# USB_ULPI_Interface.net
KiCad netlist of a schematic drawn in Altium Designer
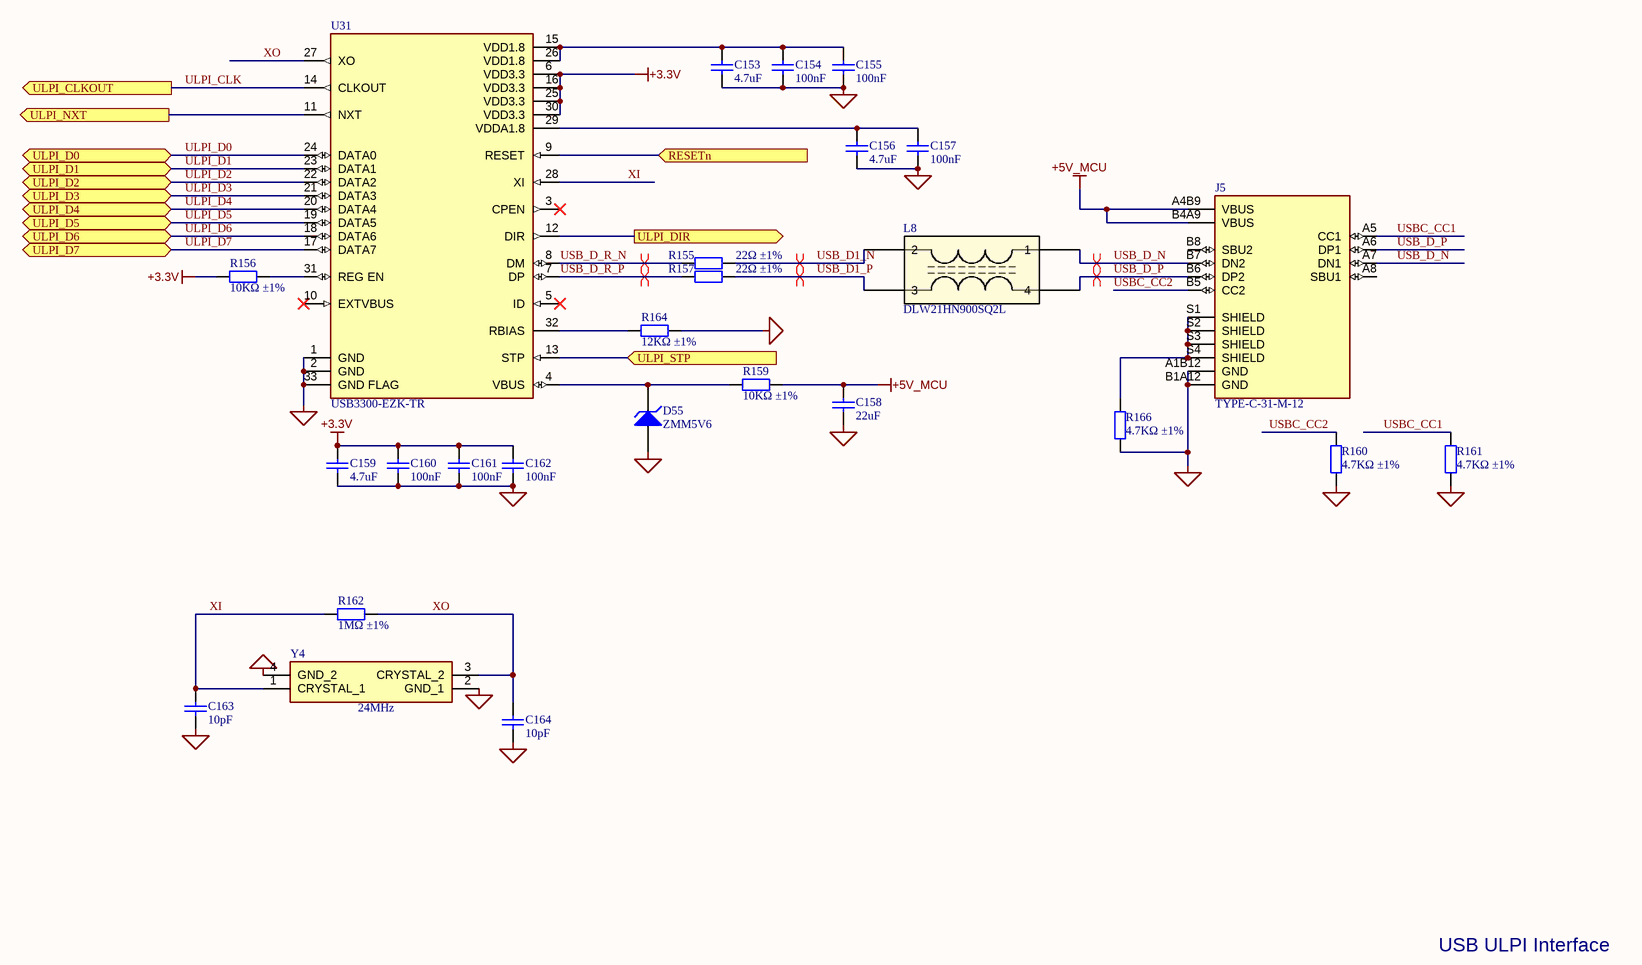
[diagram p0: USB_ULPI_Interface.SchDoc]

(export (version "E")
  (design (tool "Eeschema 10.0.6"))
  (components
    (comp (ref "C153")
      (value "4.7uF")
      (footprint "0603_C")
      (description "Chip capacitors")
      (fields
        (field (name "MANUFACTURER") "Samsung Electro-Mechanics")
        (field (name "PARTNUMBER") "CL10A475KO8NNNC")
      )
      (libsource (lib "Cap") (part "0603 4.7uF (475) 10% 16V"))
    )
    (comp (ref "C154")
      (value "100nF")
      (footprint "0402_C")
      (description "Chip capacitors")
      (fields
        (field (name "MANUFACTURER") "Samsung Electro-Mechanics")
        (field (name "PARTNUMBER") "CL05B104KO5NNNC")
      )
      (libsource (lib "Cap") (part "0402 100nF (104) 10% 16V"))
    )
    (comp (ref "C155")
      (value "100nF")
      (footprint "0402_C")
      (description "Chip capacitors")
      (fields
        (field (name "MANUFACTURER") "Samsung Electro-Mechanics")
        (field (name "PARTNUMBER") "CL05B104KO5NNNC")
      )
      (libsource (lib "Cap") (part "0402 100nF (104) 10% 16V"))
    )
    (comp (ref "C156")
      (value "4.7uF")
      (footprint "0603_C")
      (description "Chip capacitors")
      (fields
        (field (name "MANUFACTURER") "Samsung Electro-Mechanics")
        (field (name "PARTNUMBER") "CL10A475KO8NNNC")
      )
      (libsource (lib "Cap") (part "0603 4.7uF (475) 10% 16V"))
    )
    (comp (ref "C157")
      (value "100nF")
      (footprint "0402_C")
      (description "Chip capacitors")
      (fields
        (field (name "MANUFACTURER") "Samsung Electro-Mechanics")
        (field (name "PARTNUMBER") "CL05B104KO5NNNC")
      )
      (libsource (lib "Cap") (part "0402 100nF (104) 10% 16V"))
    )
    (comp (ref "C158")
      (value "22uF")
      (footprint "0805_C")
      (description "Chip capacitors")
      (fields
        (field (name "MANUFACTURER") "Samsung Electro-Mechanics")
        (field (name "PARTNUMBER") "CL21A226MAQNNNE")
      )
      (libsource (lib "Cap") (part "0805 22uF (226) 20% 25V"))
    )
    (comp (ref "C159")
      (value "4.7uF")
      (footprint "0603_C")
      (description "Chip capacitors")
      (fields
        (field (name "MANUFACTURER") "Samsung Electro-Mechanics")
        (field (name "PARTNUMBER") "CL10A475KO8NNNC")
      )
      (libsource (lib "Cap") (part "0603 4.7uF (475) 10% 16V"))
    )
    (comp (ref "C160")
      (value "100nF")
      (footprint "0402_C")
      (description "Chip capacitors")
      (fields
        (field (name "MANUFACTURER") "Samsung Electro-Mechanics")
        (field (name "PARTNUMBER") "CL05B104KO5NNNC")
      )
      (libsource (lib "Cap") (part "0402 100nF (104) 10% 16V"))
    )
    (comp (ref "C161")
      (value "100nF")
      (footprint "0402_C")
      (description "Chip capacitors")
      (fields
        (field (name "MANUFACTURER") "Samsung Electro-Mechanics")
        (field (name "PARTNUMBER") "CL05B104KO5NNNC")
      )
      (libsource (lib "Cap") (part "0402 100nF (104) 10% 16V"))
    )
    (comp (ref "C162")
      (value "100nF")
      (footprint "0402_C")
      (description "Chip capacitors")
      (fields
        (field (name "MANUFACTURER") "Samsung Electro-Mechanics")
        (field (name "PARTNUMBER") "CL05B104KO5NNNC")
      )
      (libsource (lib "Cap") (part "0402 100nF (104) 10% 16V"))
    )
    (comp (ref "C163")
      (value "10pF")
      (footprint "0402_C")
      (description "Chip capacitors")
      (fields
        (field (name "MANUFACTURER") "Samsung Electro-Mechanics")
        (field (name "MANUFACTURER PART NUMBER") "CL05C100JB5NNNC")
      )
      (libsource (lib "Cap") (part "0402 10pF (100) 5% 50V"))
    )
    (comp (ref "C164")
      (value "10pF")
      (footprint "0402_C")
      (description "Chip capacitors")
      (fields
        (field (name "MANUFACTURER") "Samsung Electro-Mechanics")
        (field (name "MANUFACTURER PART NUMBER") "CL05C100JB5NNNC")
      )
      (libsource (lib "Cap") (part "0402 10pF (100) 5% 50V"))
    )
    (comp (ref "D55")
      (value "ZMM5V6")
      (footprint "LL-34")
      (description "500mW - 0.1uA @ 1V 5.6V LL-34 Zener Diodes ROHS")
      (libsource (lib "Zener") (part "LL-34 ZMM5V6"))
    )
    (comp (ref "J5")
      (value "TYPE-C-31-M-12")
      (footprint "HRO_TYPE-C-31-M-12")
      (description "USB Connectors 24 Receptacle 1 8.94*7.3mm RoHS")
      (fields (field (name "MF") "HRO Electronics Co., Ltd."))
      (libsource (lib "Universal_CNC_Breakout") (part "TYPE-C-31-M-12"))
    )
    (comp (ref "L8")
      (value "DLW21HN900SQ2L")
      (footprint "DLW21HN121HQ2B")
      (description "90Ω@100MHz -40℃~+85℃ 350mΩ 50V 2 330mA 125V SMD-4P Common Mode Filters ROHS")
      (fields (field (name "MANUFACTURER") "Murata Electronics"))
      (libsource (lib "Sienci_Labs") (part "DLW21HN900SQ2L"))
    )
    (comp (ref "R155")
      (value "22Ω ±1%")
      (footprint "0603_R")
      (description "Chip resistor")
      (fields (field (name "MANUFACTURER") "Uniroyal Elec") (field (name "PARTNUMBER") "0603WAF220JT5E"))
      (libsource (lib "RES") (part "0603 22R (22R0) 1%"))
    )
    (comp (ref "R156")
      (value "10KΩ ±1%")
      (footprint "0402_R")
      (description "Chip resistor")
      (fields (field (name "MANUFACTURER") "Uniroyal Elec") (field (name "PARTNUMBER") "0402WGF1002TCE"))
      (libsource (lib "RES") (part "0402 10K (1002) 1%"))
    )
    (comp (ref "R157")
      (value "22Ω ±1%")
      (footprint "0603_R")
      (description "Chip resistor")
      (fields (field (name "MANUFACTURER") "Uniroyal Elec") (field (name "PARTNUMBER") "0603WAF220JT5E"))
      (libsource (lib "RES") (part "0603 22R (22R0) 1%"))
    )
    (comp (ref "R159")
      (value "10KΩ ±1%")
      (footprint "0402_R")
      (description "Chip resistor")
      (fields (field (name "MANUFACTURER") "Uniroyal Elec") (field (name "PARTNUMBER") "0402WGF1002TCE"))
      (libsource (lib "RES") (part "0402 10K (1002) 1%"))
    )
    (comp (ref "R160")
      (value "4.7KΩ ±1%")
      (footprint "0402_R")
      (description "Chip resistor")
      (fields (field (name "MANUFACTURER") "Uniroyal Elec") (field (name "PARTNUMBER") "0402WGF4701TCE"))
      (libsource (lib "RES") (part "0402 4.7K (4701) 1%"))
    )
    (comp (ref "R161")
      (value "4.7KΩ ±1%")
      (footprint "0402_R")
      (description "Chip resistor")
      (fields (field (name "MANUFACTURER") "Uniroyal Elec") (field (name "PARTNUMBER") "0402WGF4701TCE"))
      (libsource (lib "RES") (part "0402 4.7K (4701) 1%"))
    )
    (comp (ref "R162")
      (value "1MΩ ±1%")
      (footprint "0402_R")
      (description "Chip resistor")
      (fields
        (field (name "MANUFACTURER") "Uniroyal Elec")
        (field (name "MANUFACTURER PART NUMBER") "0402WGF1004TCE")
      )
      (libsource (lib "RES") (part "0402 1M (1004) 1%"))
    )
    (comp (ref "R164")
      (value "12KΩ ±1%")
      (footprint "0603_R")
      (description "Chip resistor")
      (fields (field (name "MANUFACTURER") "Uniroyal Elec") (field (name "PARTNUMBER") "0603WAF1202T5E"))
      (libsource (lib "RES") (part "0603 12K (1202) 1%"))
    )
    (comp (ref "R166")
      (value "4.7KΩ ±1%")
      (footprint "0402_R")
      (description "Chip resistor")
      (fields (field (name "MANUFACTURER") "Uniroyal Elec") (field (name "PARTNUMBER") "0402WGF4701TCE"))
      (libsource (lib "RES") (part "0402 4.7K (4701) 1%"))
    )
    (comp (ref "U31")
      (value "USB3300-EZK-TR")
      (footprint "FP-32QFN-3304-5X5B-MFG")
      (description "IC CONTROLLER USB 32QFN")
      (fields
        (field (name "MANUFACTURER") "Microchip")
        (field (name "OCTOPART") "https://octopart.com/usb3300-ezk-tr-microchip-24995444")
      )
      (libsource (lib "Altium Content Vault") (part "4aa10816561f241a170599044d3291b"))
    )
    (comp (ref "Y4")
      (value "24MHz")
      (footprint "YSX321SL")
      (description "24MHz SMD Crystal Resonator 20pF ±10ppm ±30ppm -40℃~+85℃ SMD3225-4P Crystals ROHS")
      (fields
        (field (name "MANUFACTURER") "Yangxing Tech")
        (field (name "MANUFACTURER PART NUMBER") "X322524MSB4SI")
      )
      (libsource (lib "Sienci_Labs") (part "X322525MSB4SI"))
    )
  )
  (nets
    (net (code "1") (name "+3.3V") (class "Default")
      (node (ref "C159") (pin "2") (pinfunction "2_2") (pintype "passive"))
      (node (ref "C160") (pin "2") (pinfunction "2_2") (pintype "passive"))
      (node (ref "C161") (pin "2") (pinfunction "2_2") (pintype "passive"))
      (node (ref "C162") (pin "2") (pinfunction "2_2") (pintype "passive"))
      (node (ref "R156") (pin "1") (pinfunction "1_1") (pintype "passive"))
      (node (ref "U31") (pin "16") (pinfunction "VDD3.3_16") (pintype "power_in"))
      (node (ref "U31") (pin "25") (pinfunction "VDD3.3_25") (pintype "power_in"))
      (node (ref "U31") (pin "30") (pinfunction "VDD3.3_30") (pintype "power_in"))
      (node (ref "U31") (pin "6") (pinfunction "VDD3.3_6") (pintype "power_in"))
    )
    (net (code "2") (name "+5V_MCU") (class "Default")
      (node (ref "C158") (pin "2") (pinfunction "2_2") (pintype "passive"))
      (node (ref "J5") (pin "A4B9") (pinfunction "VBUS_A4B9") (pintype "power_in"))
      (node (ref "J5") (pin "B4A9") (pinfunction "VBUS_B4A9") (pintype "power_in"))
      (node (ref "R159") (pin "2") (pinfunction "2_2") (pintype "passive"))
    )
    (net (code "3") (name "/RESETn") (class "Default")
      (node (ref "U31") (pin "9") (pinfunction "RESET_9") (pintype "input"))
    )
    (net (code "4") (name "/ULPI_CLK") (class "Default")
      (node (ref "U31") (pin "14") (pinfunction "CLKOUT_14") (pintype "output"))
    )
    (net (code "5") (name "/ULPI_D0") (class "Default")
      (node (ref "U31") (pin "24") (pinfunction "DATA0_24") (pintype "bidirectional"))
    )
    (net (code "6") (name "/ULPI_D1") (class "Default")
      (node (ref "U31") (pin "23") (pinfunction "DATA1_23") (pintype "bidirectional"))
    )
    (net (code "7") (name "/ULPI_D2") (class "Default")
      (node (ref "U31") (pin "22") (pinfunction "DATA2_22") (pintype "bidirectional"))
    )
    (net (code "8") (name "/ULPI_D3") (class "Default")
      (node (ref "U31") (pin "21") (pinfunction "DATA3_21") (pintype "bidirectional"))
    )
    (net (code "9") (name "/ULPI_D4") (class "Default")
      (node (ref "U31") (pin "20") (pinfunction "DATA4_20") (pintype "bidirectional"))
    )
    (net (code "10") (name "/ULPI_D5") (class "Default")
      (node (ref "U31") (pin "19") (pinfunction "DATA5_19") (pintype "bidirectional"))
    )
    (net (code "11") (name "/ULPI_D6") (class "Default")
      (node (ref "U31") (pin "18") (pinfunction "DATA6_18") (pintype "bidirectional"))
    )
    (net (code "12") (name "/ULPI_D7") (class "Default")
      (node (ref "U31") (pin "17") (pinfunction "DATA7_17") (pintype "bidirectional"))
    )
    (net (code "13") (name "/ULPI_DIR") (class "Default")
      (node (ref "U31") (pin "12") (pinfunction "DIR_12") (pintype "output"))
    )
    (net (code "14") (name "/ULPI_NXT") (class "Default")
      (node (ref "U31") (pin "11") (pinfunction "NXT_11") (pintype "output"))
    )
    (net (code "15") (name "/ULPI_STP") (class "Default")
      (node (ref "U31") (pin "13") (pinfunction "STP_13") (pintype "input"))
    )
    (net (code "16") (name "/USBC_CC1") (class "Default")
      (node (ref "J5") (pin "A5") (pinfunction "CC1_A5") (pintype "bidirectional"))
      (node (ref "R161") (pin "1") (pinfunction "1_1") (pintype "passive"))
    )
    (net (code "17") (name "/USBC_CC2") (class "Default")
      (node (ref "J5") (pin "B5") (pinfunction "CC2_B5") (pintype "bidirectional"))
      (node (ref "R160") (pin "1") (pinfunction "1_1") (pintype "passive"))
    )
    (net (code "18") (name "/USB_D1_N") (class "Default")
      (node (ref "L8") (pin "2") (pinfunction "2_2") (pintype "passive"))
      (node (ref "R155") (pin "2") (pinfunction "2_2") (pintype "passive"))
    )
    (net (code "19") (name "/USB_D1_P") (class "Default")
      (node (ref "L8") (pin "3") (pinfunction "3_3") (pintype "passive"))
      (node (ref "R157") (pin "2") (pinfunction "2_2") (pintype "passive"))
    )
    (net (code "20") (name "/USB_D_N") (class "Default")
      (node (ref "J5") (pin "A7") (pinfunction "DN1_A7") (pintype "bidirectional"))
      (node (ref "J5") (pin "B7") (pinfunction "DN2_B7") (pintype "bidirectional"))
      (node (ref "L8") (pin "1") (pinfunction "1_1") (pintype "passive"))
    )
    (net (code "21") (name "/USB_D_P") (class "Default")
      (node (ref "J5") (pin "A6") (pinfunction "DP1_A6") (pintype "bidirectional"))
      (node (ref "J5") (pin "B6") (pinfunction "DP2_B6") (pintype "bidirectional"))
      (node (ref "L8") (pin "4") (pinfunction "4_4") (pintype "passive"))
    )
    (net (code "22") (name "/USB_D_R_N") (class "Default")
      (node (ref "R155") (pin "1") (pinfunction "1_1") (pintype "passive"))
      (node (ref "U31") (pin "8") (pinfunction "DM_8") (pintype "bidirectional"))
    )
    (net (code "23") (name "/USB_D_R_P") (class "Default")
      (node (ref "R157") (pin "1") (pinfunction "1_1") (pintype "passive"))
      (node (ref "U31") (pin "7") (pinfunction "DP_7") (pintype "bidirectional"))
    )
    (net (code "24") (name "/XI") (class "Default")
      (node (ref "C163") (pin "2") (pinfunction "2_2") (pintype "passive"))
      (node (ref "R162") (pin "1") (pinfunction "1_1") (pintype "passive"))
      (node (ref "U31") (pin "28") (pinfunction "XI_28") (pintype "input"))
      (node (ref "Y4") (pin "1") (pinfunction "CRYSTAL_1_1") (pintype "passive"))
    )
    (net (code "25") (name "/XO") (class "Default")
      (node (ref "C164") (pin "2") (pinfunction "2_2") (pintype "passive"))
      (node (ref "R162") (pin "2") (pinfunction "2_2") (pintype "passive"))
      (node (ref "U31") (pin "27") (pinfunction "XO_27") (pintype "output"))
      (node (ref "Y4") (pin "3") (pinfunction "CRYSTAL_2_3") (pintype "passive"))
    )
    (net (code "26") (name "MCU_GND") (class "Default")
      (node (ref "C153") (pin "1") (pinfunction "1_1") (pintype "passive"))
      (node (ref "C154") (pin "1") (pinfunction "1_1") (pintype "passive"))
      (node (ref "C155") (pin "1") (pinfunction "1_1") (pintype "passive"))
      (node (ref "C156") (pin "1") (pinfunction "1_1") (pintype "passive"))
      (node (ref "C157") (pin "1") (pinfunction "1_1") (pintype "passive"))
      (node (ref "C158") (pin "1") (pinfunction "1_1") (pintype "passive"))
      (node (ref "C159") (pin "1") (pinfunction "1_1") (pintype "passive"))
      (node (ref "C160") (pin "1") (pinfunction "1_1") (pintype "passive"))
      (node (ref "C161") (pin "1") (pinfunction "1_1") (pintype "passive"))
      (node (ref "C162") (pin "1") (pinfunction "1_1") (pintype "passive"))
      (node (ref "C163") (pin "1") (pinfunction "1_1") (pintype "passive"))
      (node (ref "C164") (pin "1") (pinfunction "1_1") (pintype "passive"))
      (node (ref "D55") (pin "1") (pinfunction "A_1") (pintype "passive"))
      (node (ref "J5") (pin "A1B12") (pinfunction "GND_A1B12") (pintype "power_in"))
      (node (ref "J5") (pin "B1A12") (pinfunction "GND_B1A12") (pintype "power_in"))
      (node (ref "R160") (pin "2") (pinfunction "2_2") (pintype "passive"))
      (node (ref "R161") (pin "2") (pinfunction "2_2") (pintype "passive"))
      (node (ref "R164") (pin "2") (pinfunction "2_2") (pintype "passive"))
      (node (ref "R166") (pin "2") (pinfunction "2_2") (pintype "passive"))
      (node (ref "U31") (pin "1") (pinfunction "GND_1") (pintype "power_in"))
      (node (ref "U31") (pin "2") (pinfunction "GND_2") (pintype "power_in"))
      (node (ref "U31") (pin "33") (pinfunction "GND_FLAG_33") (pintype "power_in"))
      (node (ref "Y4") (pin "2") (pinfunction "GND_1_2") (pintype "passive"))
      (node (ref "Y4") (pin "4") (pinfunction "GND_2_4") (pintype "passive"))
    )
    (net (code "27") (name "Net-(C153-Pad2)") (class "Default")
      (node (ref "C153") (pin "2") (pinfunction "2_2") (pintype "passive"))
      (node (ref "C154") (pin "2") (pinfunction "2_2") (pintype "passive"))
      (node (ref "C155") (pin "2") (pinfunction "2_2") (pintype "passive"))
      (node (ref "U31") (pin "15") (pinfunction "VDD1.8_15") (pintype "power_in"))
      (node (ref "U31") (pin "26") (pinfunction "VDD1.8_26") (pintype "power_in"))
    )
    (net (code "28") (name "Net-(D55-K)") (class "Default")
      (node (ref "D55") (pin "2") (pinfunction "K_2") (pintype "passive"))
      (node (ref "R159") (pin "1") (pinfunction "1_1") (pintype "passive"))
      (node (ref "U31") (pin "4") (pinfunction "VBUS_4") (pintype "bidirectional"))
    )
    (net (code "29") (name "Net-(J5-SHIELD-PadS1)") (class "Default")
      (node (ref "J5") (pin "S1") (pinfunction "SHIELD_S1") (pintype "passive"))
      (node (ref "J5") (pin "S2") (pinfunction "SHIELD_S2") (pintype "passive"))
      (node (ref "J5") (pin "S3") (pinfunction "SHIELD_S3") (pintype "passive"))
      (node (ref "J5") (pin "S4") (pinfunction "SHIELD_S4") (pintype "passive"))
      (node (ref "R166") (pin "1") (pinfunction "1_1") (pintype "passive"))
    )
    (net (code "30") (name "Net-(U31-RBIAS)") (class "Default")
      (node (ref "R164") (pin "1") (pinfunction "1_1") (pintype "passive"))
      (node (ref "U31") (pin "32") (pinfunction "RBIAS_32") (pintype "power_in"))
    )
    (net (code "31") (name "Net-(U31-REG_EN)") (class "Default")
      (node (ref "R156") (pin "2") (pinfunction "2_2") (pintype "passive"))
      (node (ref "U31") (pin "31") (pinfunction "REG_EN_31") (pintype "bidirectional"))
    )
    (net (code "32") (name "Net-(U31-VDDA1.8)") (class "Default")
      (node (ref "C156") (pin "2") (pinfunction "2_2") (pintype "passive"))
      (node (ref "C157") (pin "2") (pinfunction "2_2") (pintype "passive"))
      (node (ref "U31") (pin "29") (pinfunction "VDDA1.8_29") (pintype "power_in"))
    )
    (net (code "33") (name "unconnected-(J5-SBU1-PadA8)") (class "Default")
      (node (ref "J5") (pin "A8") (pinfunction "SBU1_A8") (pintype "bidirectional"))
    )
    (net (code "34") (name "unconnected-(J5-SBU2-PadB8)") (class "Default")
      (node (ref "J5") (pin "B8") (pinfunction "SBU2_B8") (pintype "bidirectional"))
    )
    (net (code "35") (name "unconnected-(U31-CPEN-Pad3)") (class "Default")
      (node (ref "U31") (pin "3") (pinfunction "CPEN_3") (pintype "output+no_connect"))
    )
    (net (code "36") (name "unconnected-(U31-EXTVBUS-Pad10)") (class "Default")
      (node (ref "U31") (pin "10") (pinfunction "EXTVBUS_10") (pintype "input+no_connect"))
    )
    (net (code "37") (name "unconnected-(U31-ID-Pad5)") (class "Default")
      (node (ref "U31") (pin "5") (pinfunction "ID_5") (pintype "input+no_connect"))
    )
  )
)
